# Model2_v1_0.net
KiCad netlist of a schematic drawn in Altium Designer
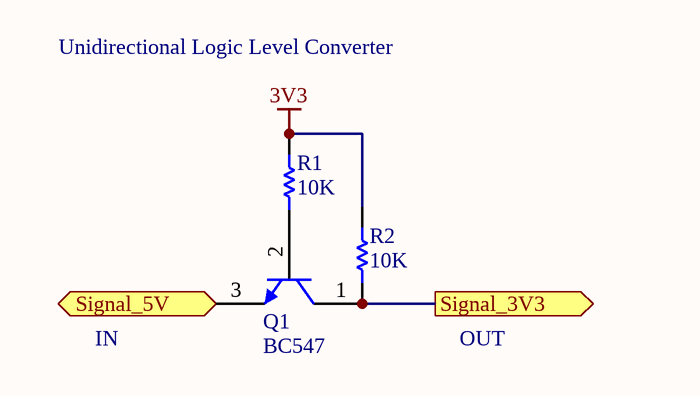
[diagram p0: Model2_v1.0.SchDoc]

(export (version "E")
  (design (tool "Eeschema 10.0.6"))
  (components
    (comp (ref "Q1")
      (value "BC547")
      (footprint "TO92_3Pin")
      (description "Transistor, BJT, NPN")
      (libsource (lib "General") (part "Transistor_BJT_NPN_cbe"))
    )
    (comp (ref "R1")
      (value "10K")
      (footprint "SMD_0805")
      (description "Resistor, 1/4W, 5%")
      (libsource (lib "General") (part "Resistor"))
    )
    (comp (ref "R2")
      (value "10K")
      (footprint "SMD_0805")
      (description "Resistor, 1/4W, 5%")
      (libsource (lib "General") (part "Resistor"))
    )
  )
  (nets
    (net (code "1") (name "/Signal_3V3") (class "Default")
      (node (ref "Q1") (pin "1") (pinfunction "C_1") (pintype "passive"))
      (node (ref "R2") (pin "1") (pinfunction "1_1") (pintype "passive"))
    )
    (net (code "2") (name "/Signal_5V") (class "Default")
      (node (ref "Q1") (pin "3") (pinfunction "E_3") (pintype "passive"))
    )
    (net (code "3") (name "3V3") (class "Default")
      (node (ref "R1") (pin "2") (pinfunction "2_2") (pintype "passive"))
      (node (ref "R2") (pin "2") (pinfunction "2_2") (pintype "passive"))
    )
    (net (code "4") (name "Net-(Q1-B)") (class "Default")
      (node (ref "Q1") (pin "2") (pinfunction "B_2") (pintype "passive"))
      (node (ref "R1") (pin "1") (pinfunction "1_1") (pintype "passive"))
    )
  )
)
